# USB-UART-Board-CP2102N_v9.net
KiCad netlist of a schematic drawn in EAGLE
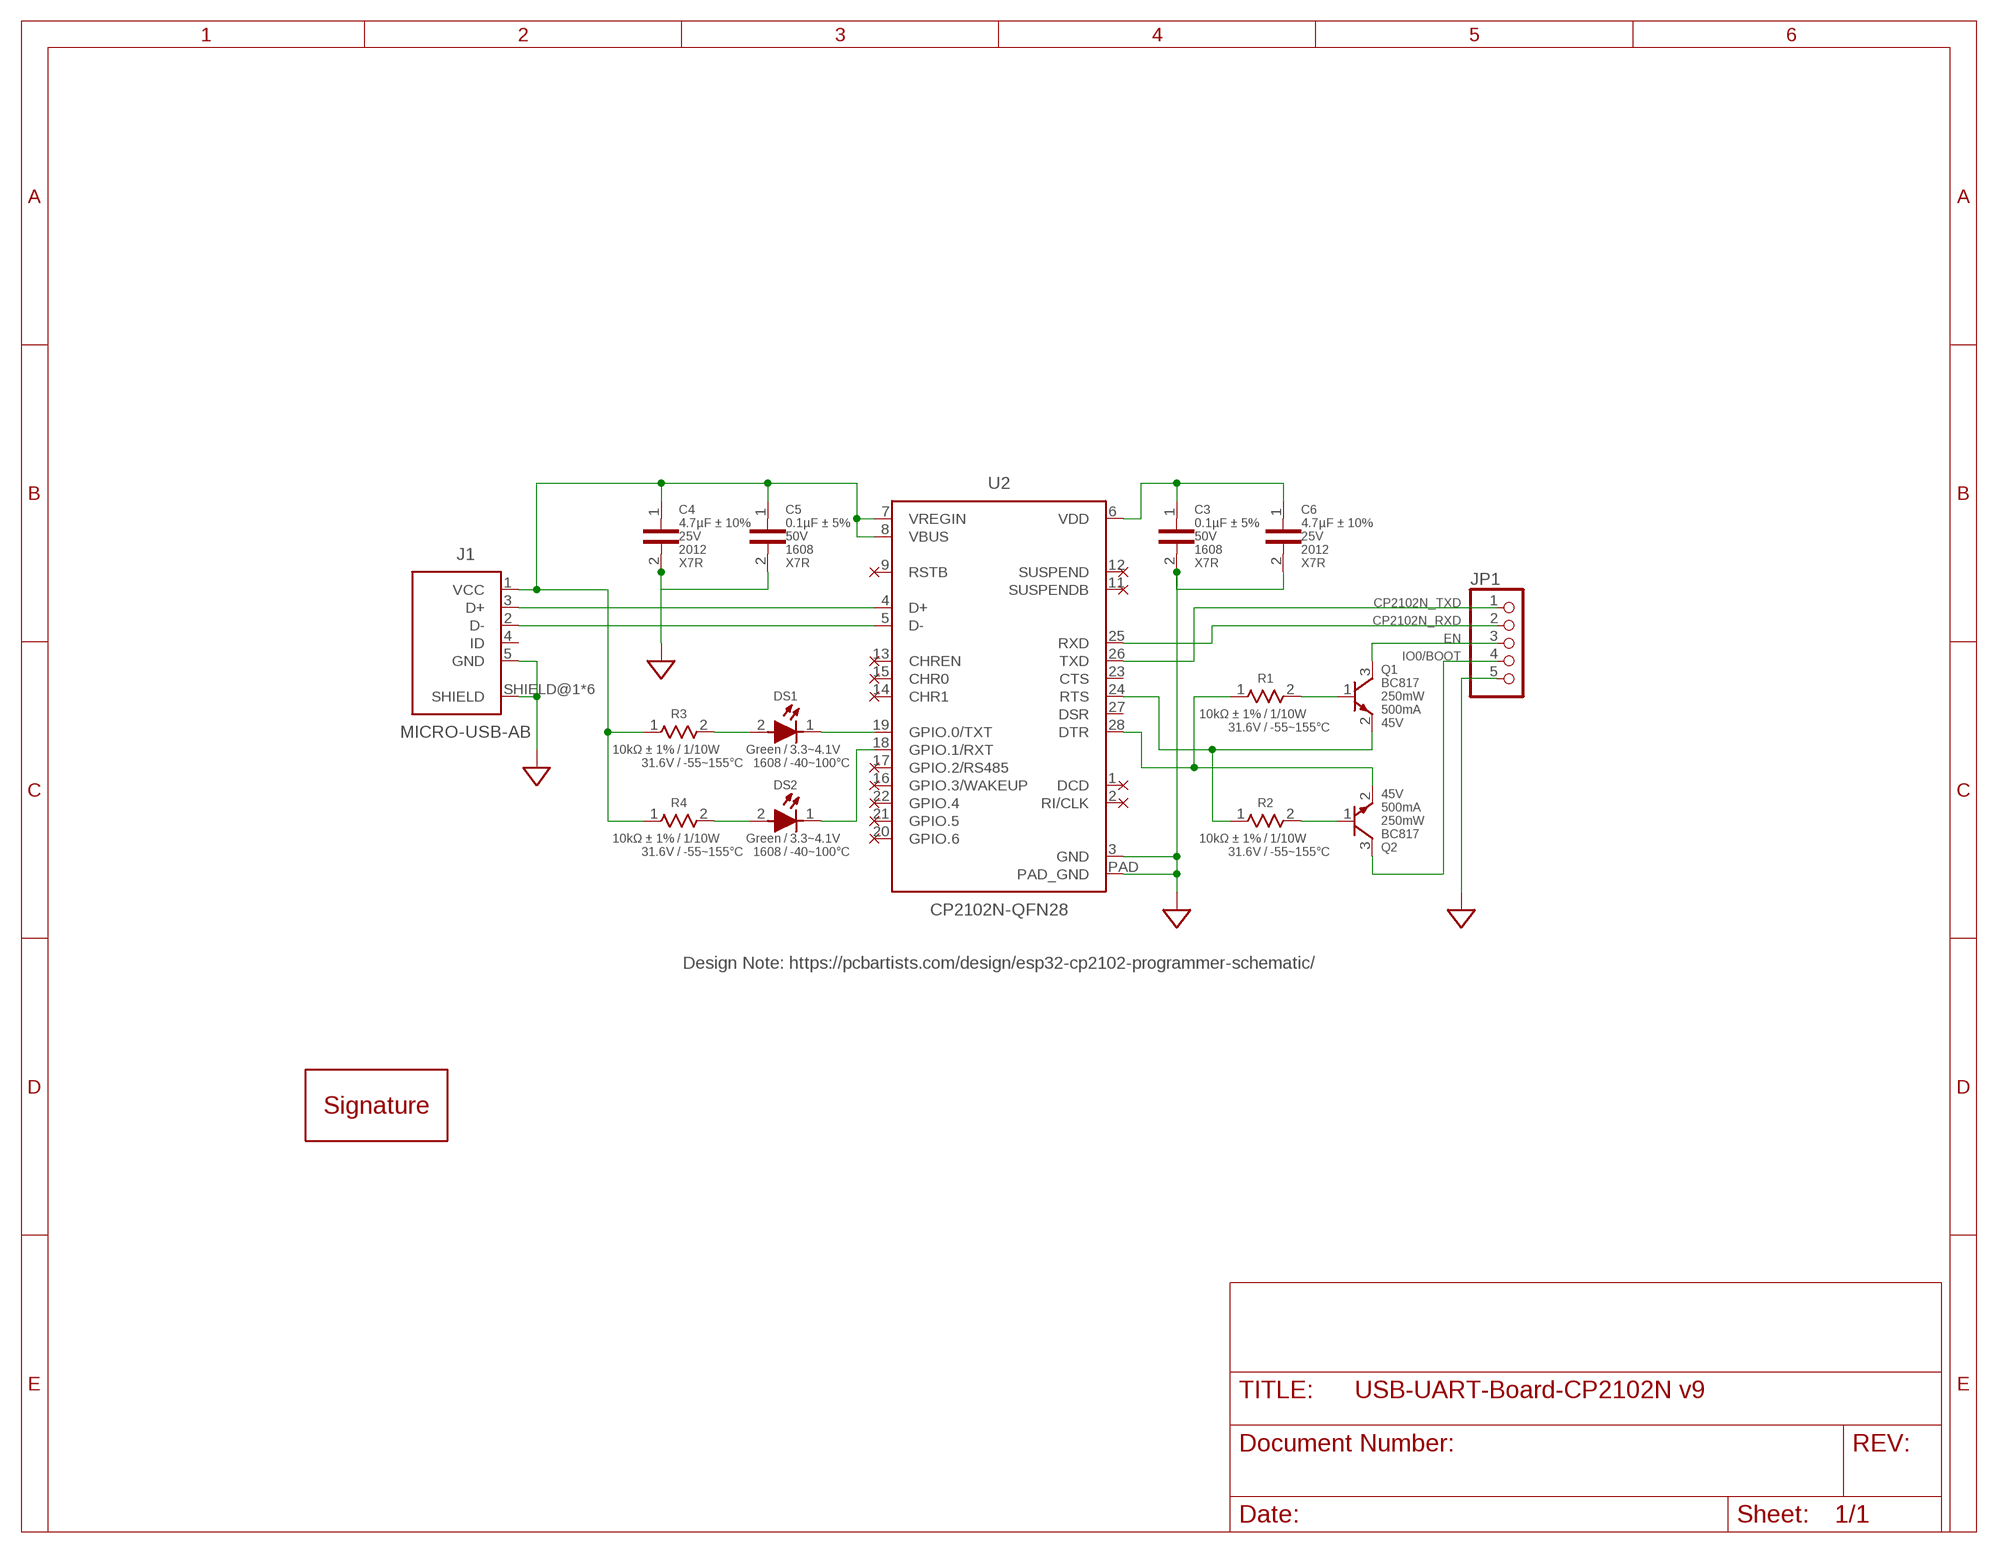
[diagram p0: schematic, sheet 1]

(export (version "E")
  (design (tool "Eeschema 10.0.6"))
  (components
    (comp (ref "C3")
      (value "0.1µF ± 5%")
      (footprint "eagle-import:1608-SEM")
      (fields (field (name "SIZE") "1608") (field (name "TEMPERATURE") "X7R") (field (name "VOLTAGE") "50V"))
      (libsource (lib "eagle-import") (part "CAP-V-1608-0.1UF"))
    )
    (comp (ref "C4")
      (value "4.7µF ± 10%")
      (footprint "eagle-import:2012-SEM")
      (fields (field (name "SIZE") "2012") (field (name "TEMPERATURE") "X7R") (field (name "VOLTAGE") "25V"))
      (libsource (lib "eagle-import") (part "CAP-V-2012-4.7UF"))
    )
    (comp (ref "C5")
      (value "0.1µF ± 5%")
      (footprint "eagle-import:1608-SEM")
      (fields (field (name "SIZE") "1608") (field (name "TEMPERATURE") "X7R") (field (name "VOLTAGE") "50V"))
      (libsource (lib "eagle-import") (part "CAP-V-1608-0.1UF"))
    )
    (comp (ref "C6")
      (value "4.7µF ± 10%")
      (footprint "eagle-import:2012-SEM")
      (fields (field (name "SIZE") "2012") (field (name "TEMPERATURE") "X7R") (field (name "VOLTAGE") "25V"))
      (libsource (lib "eagle-import") (part "CAP-V-2012-4.7UF"))
    )
    (comp (ref "DS1")
      (value "Green")
      (footprint "eagle-import:1608")
      (fields
        (field (name "SIZE") "1608")
        (field (name "TEMPERATURE") "-40~100°C")
        (field (name "VOLTAGE") "3.3~4.1V")
      )
      (libsource (lib "eagle-import") (part "LED-H-1608-GREEN"))
    )
    (comp (ref "DS2")
      (value "Green")
      (footprint "eagle-import:1608")
      (fields
        (field (name "SIZE") "1608")
        (field (name "TEMPERATURE") "-40~100°C")
        (field (name "VOLTAGE") "3.3~4.1V")
      )
      (libsource (lib "eagle-import") (part "LED-H-1608-GREEN"))
    )
    (comp (ref "J1")
      (value "MICRO-USB-AB")
      (footprint "eagle-import:47589-0001")
      (libsource (lib "eagle-import") (part "MICRO-USB-AB"))
    )
    (comp (ref "JP1")
      (value "PINHD-1X5")
      (footprint "eagle-import:1X05")
      (libsource (lib "eagle-import") (part "PINHD-1X5"))
    )
    (comp (ref "Q1")
      (value "BC817")
      (footprint "eagle-import:SOT-23")
      (fields (field (name "POWER") "250mW") (field (name "IC_MAX") "500mA") (field (name "VCE_MAX") "45V"))
      (libsource (lib "eagle-import") (part "BJT-NPN-BC817"))
    )
    (comp (ref "Q2")
      (value "BC817")
      (footprint "eagle-import:SOT-23")
      (fields (field (name "POWER") "250mW") (field (name "IC_MAX") "500mA") (field (name "VCE_MAX") "45V"))
      (libsource (lib "eagle-import") (part "BJT-NPN-BC817"))
    )
    (comp (ref "R1")
      (value "10kΩ ± 1%")
      (footprint "eagle-import:1608-SEM")
      (fields
        (field (name "POWER") "1/10W")
        (field (name "TEMPERATURE") "-55~155°C")
        (field (name "VOLTAGE") "31.6V")
      )
      (libsource (lib "eagle-import") (part "RES-H-1608-10K"))
    )
    (comp (ref "R2")
      (value "10kΩ ± 1%")
      (footprint "eagle-import:1608-SEM")
      (fields
        (field (name "POWER") "1/10W")
        (field (name "TEMPERATURE") "-55~155°C")
        (field (name "VOLTAGE") "31.6V")
      )
      (libsource (lib "eagle-import") (part "RES-H-1608-10K"))
    )
    (comp (ref "R3")
      (value "10kΩ ± 1%")
      (footprint "eagle-import:1608-SEM")
      (fields
        (field (name "POWER") "1/10W")
        (field (name "TEMPERATURE") "-55~155°C")
        (field (name "VOLTAGE") "31.6V")
      )
      (libsource (lib "eagle-import") (part "RES-H-1608-10K"))
    )
    (comp (ref "R4")
      (value "10kΩ ± 1%")
      (footprint "eagle-import:1608-SEM")
      (fields
        (field (name "POWER") "1/10W")
        (field (name "TEMPERATURE") "-55~155°C")
        (field (name "VOLTAGE") "31.6V")
      )
      (libsource (lib "eagle-import") (part "RES-H-1608-10K"))
    )
    (comp (ref "U$2")
      (value "SIGNATURE")
      (footprint "eagle-import:SIGNATURE")
      (libsource (lib "eagle-import") (part "SIGNATURE"))
    )
    (comp (ref "U2")
      (value "CP2102N-QFN28")
      (footprint "eagle-import:QFN28")
      (libsource (lib "eagle-import") (part "CP2102N-QFN28"))
    )
  )
  (nets
    (net (code "1") (name "/CP2102N_RXD") (class "Default")
      (node (ref "JP1") (pin "2") (pinfunction "2_2") (pintype "passive"))
      (node (ref "U2") (pin "25") (pinfunction "RXD_25") (pintype "bidirectional"))
    )
    (net (code "2") (name "/CP2102N_TXD") (class "Default")
      (node (ref "JP1") (pin "1") (pinfunction "1_1") (pintype "passive"))
      (node (ref "U2") (pin "26") (pinfunction "TXD_26") (pintype "bidirectional"))
    )
    (net (code "3") (name "/EN") (class "Default")
      (node (ref "JP1") (pin "3") (pinfunction "3_3") (pintype "passive"))
      (node (ref "Q1") (pin "3") (pinfunction "C_3") (pintype "input"))
    )
    (net (code "4") (name "/IO0{slash}BOOT") (class "Default")
      (node (ref "JP1") (pin "4") (pinfunction "4_4") (pintype "passive"))
      (node (ref "Q2") (pin "3") (pinfunction "C_3") (pintype "input"))
    )
    (net (code "5") (name "GND") (class "Default")
      (node (ref "C3") (pin "2") (pinfunction "P$2_2") (pintype "passive"))
      (node (ref "C4") (pin "2") (pinfunction "P$2_2") (pintype "passive"))
      (node (ref "C5") (pin "2") (pinfunction "P$2_2") (pintype "passive"))
      (node (ref "C6") (pin "2") (pinfunction "P$2_2") (pintype "passive"))
      (node (ref "J1") (pin "5") (pinfunction "GND_5") (pintype "power_in"))
      (node (ref "J1") (pin "SHIELD@1") (pinfunction "SHIELD_SHIELD@1") (pintype "power_in"))
      (node (ref "J1") (pin "SHIELD@2") (pinfunction "SHIELD_SHIELD@2") (pintype "power_in"))
      (node (ref "J1") (pin "SHIELD@3") (pinfunction "SHIELD_SHIELD@3") (pintype "power_in"))
      (node (ref "J1") (pin "SHIELD@4") (pinfunction "SHIELD_SHIELD@4") (pintype "power_in"))
      (node (ref "J1") (pin "SHIELD@5") (pinfunction "SHIELD_SHIELD@5") (pintype "power_in"))
      (node (ref "J1") (pin "SHIELD@6") (pinfunction "SHIELD_SHIELD@6") (pintype "power_in"))
      (node (ref "JP1") (pin "5") (pinfunction "5_5") (pintype "passive"))
      (node (ref "U2") (pin "3") (pinfunction "GND_3") (pintype "bidirectional"))
      (node (ref "U2") (pin "PAD") (pinfunction "PAD_GND_PAD") (pintype "bidirectional"))
    )
    (net (code "6") (name "Net-(C3-P$1)") (class "Default")
      (node (ref "C3") (pin "1") (pinfunction "P$1_1") (pintype "passive"))
      (node (ref "C6") (pin "1") (pinfunction "P$1_1") (pintype "passive"))
      (node (ref "U2") (pin "6") (pinfunction "VDD_6") (pintype "bidirectional"))
    )
    (net (code "7") (name "Net-(C4-P$1)") (class "Default")
      (node (ref "C4") (pin "1") (pinfunction "P$1_1") (pintype "passive"))
      (node (ref "C5") (pin "1") (pinfunction "P$1_1") (pintype "passive"))
      (node (ref "J1") (pin "1") (pinfunction "VCC_1") (pintype "power_in"))
      (node (ref "R3") (pin "1") (pinfunction "1_1") (pintype "passive"))
      (node (ref "R4") (pin "1") (pinfunction "1_1") (pintype "passive"))
      (node (ref "U2") (pin "7") (pinfunction "VREGIN_7") (pintype "bidirectional"))
      (node (ref "U2") (pin "8") (pinfunction "VBUS_8") (pintype "bidirectional"))
    )
    (net (code "8") (name "Net-(DS1-Pad2)") (class "Default")
      (node (ref "DS1") (pin "2") (pinfunction "2_2") (pintype "input"))
      (node (ref "R3") (pin "2") (pinfunction "2_2") (pintype "passive"))
    )
    (net (code "9") (name "Net-(DS2-Pad2)") (class "Default")
      (node (ref "DS2") (pin "2") (pinfunction "2_2") (pintype "input"))
      (node (ref "R4") (pin "2") (pinfunction "2_2") (pintype "passive"))
    )
    (net (code "10") (name "Net-(J1-D+)") (class "Default")
      (node (ref "J1") (pin "3") (pinfunction "D+_3") (pintype "input"))
      (node (ref "U2") (pin "4") (pinfunction "D+_4") (pintype "bidirectional"))
    )
    (net (code "11") (name "Net-(J1-D-)") (class "Default")
      (node (ref "J1") (pin "2") (pinfunction "D-_2") (pintype "output"))
      (node (ref "U2") (pin "5") (pinfunction "D-_5") (pintype "bidirectional"))
    )
    (net (code "12") (name "Net-(Q1-B)") (class "Default")
      (node (ref "Q1") (pin "1") (pinfunction "B_1") (pintype "input"))
      (node (ref "R1") (pin "2") (pinfunction "2_2") (pintype "passive"))
    )
    (net (code "13") (name "Net-(Q1-E)") (class "Default")
      (node (ref "Q1") (pin "2") (pinfunction "E_2") (pintype "output"))
      (node (ref "R2") (pin "1") (pinfunction "1_1") (pintype "passive"))
      (node (ref "U2") (pin "24") (pinfunction "RTS_24") (pintype "bidirectional"))
    )
    (net (code "14") (name "Net-(Q2-B)") (class "Default")
      (node (ref "Q2") (pin "1") (pinfunction "B_1") (pintype "input"))
      (node (ref "R2") (pin "2") (pinfunction "2_2") (pintype "passive"))
    )
    (net (code "15") (name "Net-(Q2-E)") (class "Default")
      (node (ref "Q2") (pin "2") (pinfunction "E_2") (pintype "output"))
      (node (ref "R1") (pin "1") (pinfunction "1_1") (pintype "passive"))
      (node (ref "U2") (pin "28") (pinfunction "DTR_28") (pintype "bidirectional"))
    )
    (net (code "16") (name "Net-(U2-GPIO.0{slash}TXT)") (class "Default")
      (node (ref "DS1") (pin "1") (pinfunction "1_1") (pintype "output"))
      (node (ref "U2") (pin "19") (pinfunction "GPIO.0/TXT_19") (pintype "bidirectional"))
    )
    (net (code "17") (name "Net-(U2-GPIO.1{slash}RXT)") (class "Default")
      (node (ref "DS2") (pin "1") (pinfunction "1_1") (pintype "output"))
      (node (ref "U2") (pin "18") (pinfunction "GPIO.1/RXT_18") (pintype "bidirectional"))
    )
    (net (code "18") (name "unconnected-(J1-ID-Pad4)") (class "Default")
      (node (ref "J1") (pin "4") (pinfunction "ID_4") (pintype "no_connect"))
    )
    (net (code "19") (name "unconnected-(U2-CHR0-Pad15)") (class "Default")
      (node (ref "U2") (pin "15") (pinfunction "CHR0_15") (pintype "bidirectional"))
    )
    (net (code "20") (name "unconnected-(U2-CHR1-Pad14)") (class "Default")
      (node (ref "U2") (pin "14") (pinfunction "CHR1_14") (pintype "bidirectional"))
    )
    (net (code "21") (name "unconnected-(U2-CHREN-Pad13)") (class "Default")
      (node (ref "U2") (pin "13") (pinfunction "CHREN_13") (pintype "bidirectional"))
    )
    (net (code "22") (name "unconnected-(U2-CTS-Pad23)") (class "Default")
      (node (ref "U2") (pin "23") (pinfunction "CTS_23") (pintype "bidirectional"))
    )
    (net (code "23") (name "unconnected-(U2-DCD-Pad1)") (class "Default")
      (node (ref "U2") (pin "1") (pinfunction "DCD_1") (pintype "bidirectional"))
    )
    (net (code "24") (name "unconnected-(U2-DSR-Pad27)") (class "Default")
      (node (ref "U2") (pin "27") (pinfunction "DSR_27") (pintype "bidirectional"))
    )
    (net (code "25") (name "unconnected-(U2-GPIO.2{slash}RS485-Pad17)") (class "Default")
      (node (ref "U2") (pin "17") (pinfunction "GPIO.2/RS485_17") (pintype "bidirectional"))
    )
    (net (code "26") (name "unconnected-(U2-GPIO.3{slash}WAKEUP-Pad16)") (class "Default")
      (node (ref "U2") (pin "16") (pinfunction "GPIO.3/WAKEUP_16") (pintype "bidirectional"))
    )
    (net (code "27") (name "unconnected-(U2-GPIO.4-Pad22)") (class "Default")
      (node (ref "U2") (pin "22") (pinfunction "GPIO.4_22") (pintype "bidirectional"))
    )
    (net (code "28") (name "unconnected-(U2-GPIO.5-Pad21)") (class "Default")
      (node (ref "U2") (pin "21") (pinfunction "GPIO.5_21") (pintype "bidirectional"))
    )
    (net (code "29") (name "unconnected-(U2-GPIO.6-Pad20)") (class "Default")
      (node (ref "U2") (pin "20") (pinfunction "GPIO.6_20") (pintype "bidirectional"))
    )
    (net (code "30") (name "unconnected-(U2-RI{slash}CLK-Pad2)") (class "Default")
      (node (ref "U2") (pin "2") (pinfunction "RI/CLK_2") (pintype "bidirectional"))
    )
    (net (code "31") (name "unconnected-(U2-RSTB-Pad9)") (class "Default")
      (node (ref "U2") (pin "9") (pinfunction "RSTB_9") (pintype "bidirectional"))
    )
    (net (code "32") (name "unconnected-(U2-SUSPEND-Pad12)") (class "Default")
      (node (ref "U2") (pin "12") (pinfunction "SUSPEND_12") (pintype "bidirectional"))
    )
    (net (code "33") (name "unconnected-(U2-SUSPENDB-Pad11)") (class "Default")
      (node (ref "U2") (pin "11") (pinfunction "SUSPENDB_11") (pintype "bidirectional"))
    )
  )
)
